# Power_Supply.net
KiCad netlist of a schematic drawn in Altium Designer
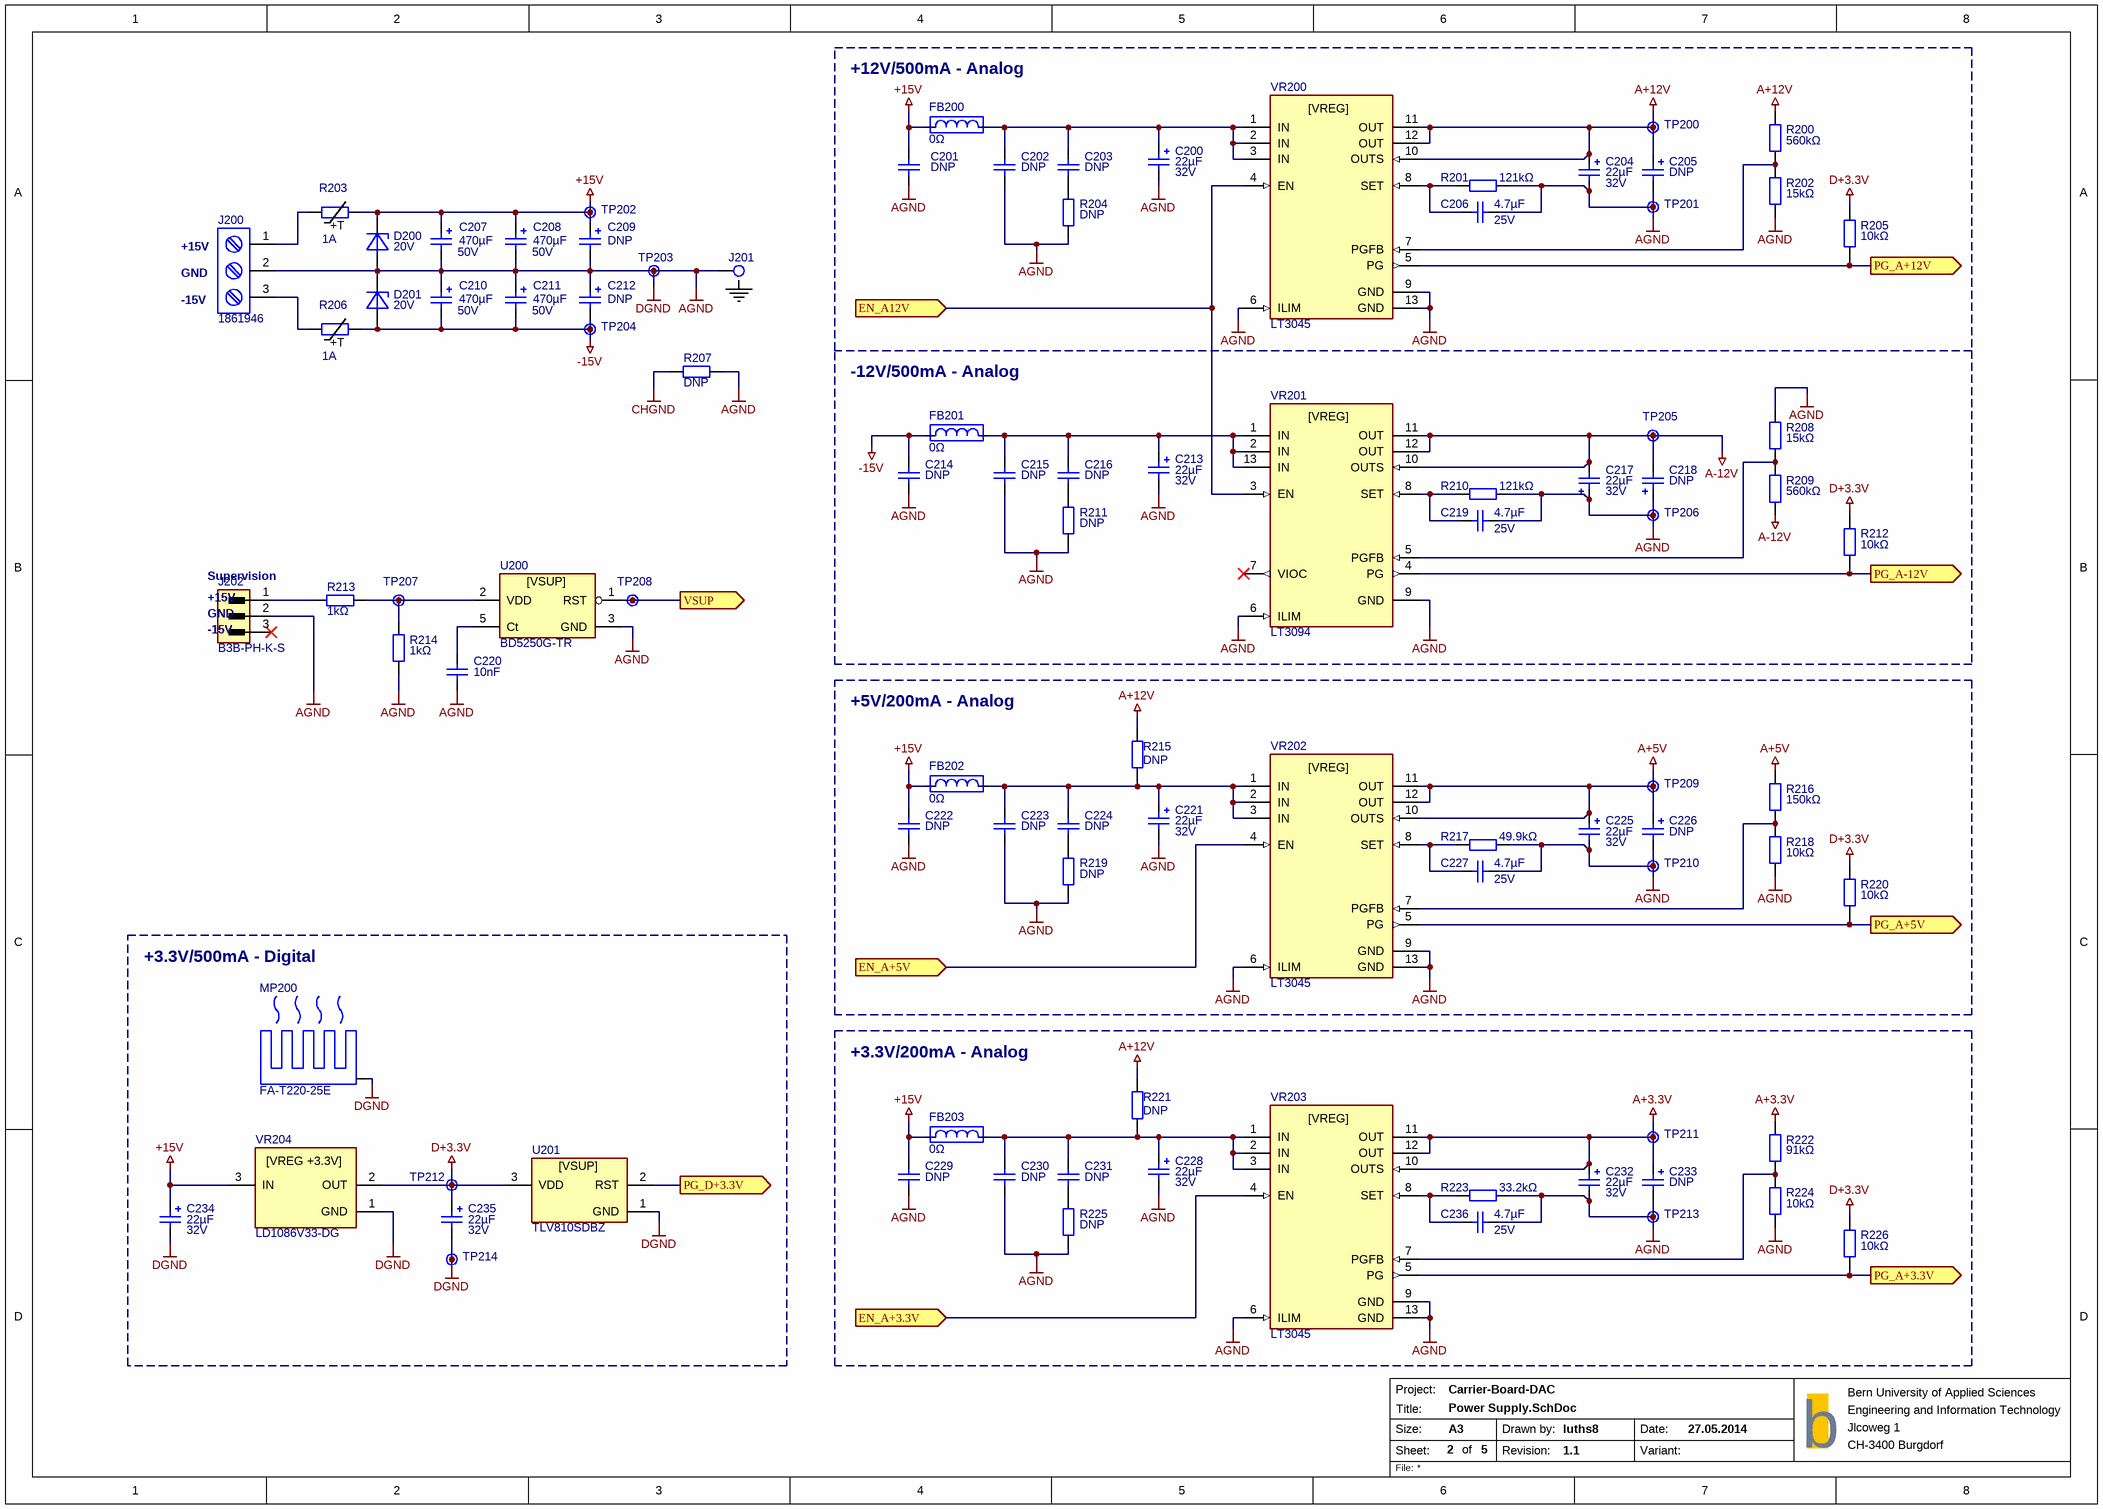
[diagram p0: Power Supply.SchDoc]

(export (version "E")
  (design (tool "Eeschema 10.0.6"))
  (components
    (comp (ref "C200")
      (value "22µF")
      (footprint "CAP-6.3-5.5-2.5")
      (description "Elektrolytic Capacitor")
      (fields (field (name "VOLTAGE") "32V") (field (name "MANUFACTURER PART NO.") "32SEPF22M"))
      (libsource (lib "Audio-Streamer") (part "Capacitor Electrolytic"))
    )
    (comp (ref "C201")
      (value "DNP")
      (footprint "SMD0805CAP")
      (description "Ceramic Capacitor")
      (fields (field (name "VOLTAGE") "25V"))
      (libsource (lib "Audio-Streamer") (part "Capacitor Ceramic"))
    )
    (comp (ref "C202")
      (value "DNP")
      (footprint "SMD0805CAP")
      (description "Ceramic Capacitor")
      (fields (field (name "VOLTAGE") "25V"))
      (libsource (lib "Audio-Streamer") (part "Capacitor Ceramic"))
    )
    (comp (ref "C203")
      (value "DNP")
      (footprint "SMD0805CAP")
      (description "Ceramic Capacitor")
      (fields (field (name "VOLTAGE") "25V"))
      (libsource (lib "Audio-Streamer") (part "Capacitor Ceramic"))
    )
    (comp (ref "C204")
      (value "22µF")
      (footprint "CAP-6.3-5.5-2.5")
      (description "Elektrolytic Capacitor")
      (fields (field (name "VOLTAGE") "32V") (field (name "MANUFACTURER PART NO.") "32SEPF22M"))
      (libsource (lib "Audio-Streamer") (part "Capacitor Electrolytic"))
    )
    (comp (ref "C205")
      (value "DNP")
      (footprint "CAP-6.3-5.5-2.5")
      (description "Elektrolytic Capacitor")
      (fields (field (name "VOLTAGE") "32V") (field (name "MANUFACTURER PART NO.") "32SEPF22M"))
      (libsource (lib "Audio-Streamer") (part "Capacitor Electrolytic"))
    )
    (comp (ref "C206")
      (value "4.7µF")
      (footprint "SMD1206CAP")
      (description "Ceramic Capacitor")
      (fields (field (name "VOLTAGE") "25V"))
      (libsource (lib "Audio-Streamer") (part "Capacitor Ceramic"))
    )
    (comp (ref "C207")
      (value "470µF")
      (footprint "CAP-12.5-20-5")
      (description "Elektrolytic Capacitor")
      (fields (field (name "VOLTAGE") "50V") (field (name "MANUFACTURER PART NO.") "EEU-FR1H471"))
      (libsource (lib "Audio-Streamer") (part "Capacitor Electrolytic"))
    )
    (comp (ref "C208")
      (value "470µF")
      (footprint "CAP-12.5-20-5")
      (description "Elektrolytic Capacitor")
      (fields (field (name "VOLTAGE") "50V") (field (name "MANUFACTURER PART NO.") "EEU-FR1H471"))
      (libsource (lib "Audio-Streamer") (part "Capacitor Electrolytic"))
    )
    (comp (ref "C209")
      (value "DNP")
      (footprint "CAP-12.5-20-5")
      (description "Elektrolytic Capacitor")
      (fields (field (name "VOLTAGE") "50V") (field (name "MANUFACTURER PART NO.") "EEU-FR1H471"))
      (libsource (lib "Audio-Streamer") (part "Capacitor Electrolytic"))
    )
    (comp (ref "C210")
      (value "470µF")
      (footprint "CAP-12.5-20-5")
      (description "Elektrolytic Capacitor")
      (fields (field (name "VOLTAGE") "50V") (field (name "MANUFACTURER PART NO.") "EEU-FR1H471"))
      (libsource (lib "Audio-Streamer") (part "Capacitor Electrolytic"))
    )
    (comp (ref "C211")
      (value "470µF")
      (footprint "CAP-12.5-20-5")
      (description "Elektrolytic Capacitor")
      (fields (field (name "VOLTAGE") "50V") (field (name "MANUFACTURER PART NO.") "EEU-FR1H471"))
      (libsource (lib "Audio-Streamer") (part "Capacitor Electrolytic"))
    )
    (comp (ref "C212")
      (value "DNP")
      (footprint "CAP-12.5-20-5")
      (description "Elektrolytic Capacitor")
      (fields (field (name "VOLTAGE") "50V") (field (name "MANUFACTURER PART NO.") "EEU-FR1H471"))
      (libsource (lib "Audio-Streamer") (part "Capacitor Electrolytic"))
    )
    (comp (ref "C213")
      (value "22µF")
      (footprint "CAP-6.3-5.5-2.5")
      (description "Elektrolytic Capacitor")
      (fields (field (name "VOLTAGE") "32V") (field (name "MANUFACTURER PART NO.") "32SEPF22M"))
      (libsource (lib "Audio-Streamer") (part "Capacitor Electrolytic"))
    )
    (comp (ref "C214")
      (value "DNP")
      (footprint "SMD0805CAP")
      (description "Ceramic Capacitor")
      (fields (field (name "VOLTAGE") "25V"))
      (libsource (lib "Audio-Streamer") (part "Capacitor Ceramic"))
    )
    (comp (ref "C215")
      (value "DNP")
      (footprint "SMD0805CAP")
      (description "Ceramic Capacitor")
      (fields (field (name "VOLTAGE") "25V"))
      (libsource (lib "Audio-Streamer") (part "Capacitor Ceramic"))
    )
    (comp (ref "C216")
      (value "DNP")
      (footprint "SMD0805CAP")
      (description "Ceramic Capacitor")
      (fields (field (name "VOLTAGE") "25V"))
      (libsource (lib "Audio-Streamer") (part "Capacitor Ceramic"))
    )
    (comp (ref "C217")
      (value "22µF")
      (footprint "CAP-6.3-5.5-2.5")
      (description "Elektrolytic Capacitor")
      (fields (field (name "VOLTAGE") "32V") (field (name "MANUFACTURER PART NO.") "32SEPF22M"))
      (libsource (lib "Audio-Streamer") (part "Capacitor Electrolytic"))
    )
    (comp (ref "C218")
      (value "DNP")
      (footprint "CAP-6.3-5.5-2.5")
      (description "Elektrolytic Capacitor")
      (fields (field (name "VOLTAGE") "32V") (field (name "MANUFACTURER PART NO.") "32SEPF22M"))
      (libsource (lib "Audio-Streamer") (part "Capacitor Electrolytic"))
    )
    (comp (ref "C219")
      (value "4.7µF")
      (footprint "SMD1206CAP")
      (description "Ceramic Capacitor")
      (fields (field (name "VOLTAGE") "25V"))
      (libsource (lib "Audio-Streamer") (part "Capacitor Ceramic"))
    )
    (comp (ref "C220")
      (value "10nF")
      (footprint "SMD0603CAP")
      (description "Ceramic Capacitor")
      (fields (field (name "VOLTAGE") "25V"))
      (libsource (lib "Audio-Streamer") (part "Capacitor Ceramic"))
    )
    (comp (ref "C221")
      (value "22µF")
      (footprint "CAP-6.3-5.5-2.5")
      (description "Elektrolytic Capacitor")
      (fields (field (name "VOLTAGE") "32V") (field (name "MANUFACTURER PART NO.") "32SEPF22M"))
      (libsource (lib "Audio-Streamer") (part "Capacitor Electrolytic"))
    )
    (comp (ref "C222")
      (value "DNP")
      (footprint "SMD0805CAP")
      (description "Ceramic Capacitor")
      (fields (field (name "VOLTAGE") "25V"))
      (libsource (lib "Audio-Streamer") (part "Capacitor Ceramic"))
    )
    (comp (ref "C223")
      (value "DNP")
      (footprint "SMD0805CAP")
      (description "Ceramic Capacitor")
      (fields (field (name "VOLTAGE") "25V"))
      (libsource (lib "Audio-Streamer") (part "Capacitor Ceramic"))
    )
    (comp (ref "C224")
      (value "DNP")
      (footprint "SMD0805CAP")
      (description "Ceramic Capacitor")
      (fields (field (name "VOLTAGE") "25V"))
      (libsource (lib "Audio-Streamer") (part "Capacitor Ceramic"))
    )
    (comp (ref "C225")
      (value "22µF")
      (footprint "CAP-6.3-5.5-2.5")
      (description "Elektrolytic Capacitor")
      (fields (field (name "VOLTAGE") "32V") (field (name "MANUFACTURER PART NO.") "32SEPF22M"))
      (libsource (lib "Audio-Streamer") (part "Capacitor Electrolytic"))
    )
    (comp (ref "C226")
      (value "DNP")
      (footprint "CAP-6.3-5.5-2.5")
      (description "Elektrolytic Capacitor")
      (fields (field (name "VOLTAGE") "32V") (field (name "MANUFACTURER PART NO.") "32SEPF22M"))
      (libsource (lib "Audio-Streamer") (part "Capacitor Electrolytic"))
    )
    (comp (ref "C227")
      (value "4.7µF")
      (footprint "SMD1206CAP")
      (description "Ceramic Capacitor")
      (fields (field (name "VOLTAGE") "25V"))
      (libsource (lib "Audio-Streamer") (part "Capacitor Ceramic"))
    )
    (comp (ref "C228")
      (value "22µF")
      (footprint "CAP-6.3-5.5-2.5")
      (description "Elektrolytic Capacitor")
      (fields (field (name "VOLTAGE") "32V") (field (name "MANUFACTURER PART NO.") "32SEPF22M"))
      (libsource (lib "Audio-Streamer") (part "Capacitor Electrolytic"))
    )
    (comp (ref "C229")
      (value "DNP")
      (footprint "SMD0805CAP")
      (description "Ceramic Capacitor")
      (fields (field (name "VOLTAGE") "25V"))
      (libsource (lib "Audio-Streamer") (part "Capacitor Ceramic"))
    )
    (comp (ref "C230")
      (value "DNP")
      (footprint "SMD0805CAP")
      (description "Ceramic Capacitor")
      (fields (field (name "VOLTAGE") "25V"))
      (libsource (lib "Audio-Streamer") (part "Capacitor Ceramic"))
    )
    (comp (ref "C231")
      (value "DNP")
      (footprint "SMD0805CAP")
      (description "Ceramic Capacitor")
      (fields (field (name "VOLTAGE") "25V"))
      (libsource (lib "Audio-Streamer") (part "Capacitor Ceramic"))
    )
    (comp (ref "C232")
      (value "22µF")
      (footprint "CAP-6.3-5.5-2.5")
      (description "Elektrolytic Capacitor")
      (fields (field (name "VOLTAGE") "32V") (field (name "MANUFACTURER PART NO.") "32SEPF22M"))
      (libsource (lib "Audio-Streamer") (part "Capacitor Electrolytic"))
    )
    (comp (ref "C233")
      (value "DNP")
      (footprint "CAP-6.3-5.5-2.5")
      (description "Elektrolytic Capacitor")
      (fields (field (name "VOLTAGE") "32V") (field (name "MANUFACTURER PART NO.") "32SEPF22M"))
      (libsource (lib "Audio-Streamer") (part "Capacitor Electrolytic"))
    )
    (comp (ref "C234")
      (value "22µF")
      (footprint "CAP-6.3-5.5-2.5")
      (description "Elektrolytic Capacitor")
      (fields (field (name "VOLTAGE") "32V") (field (name "MANUFACTURER PART NO.") "32SEPF22M"))
      (libsource (lib "Audio-Streamer") (part "Capacitor Electrolytic"))
    )
    (comp (ref "C235")
      (value "22µF")
      (footprint "CAP-6.3-5.5-2.5")
      (description "Elektrolytic Capacitor")
      (fields (field (name "VOLTAGE") "32V") (field (name "MANUFACTURER PART NO.") "32SEPF22M"))
      (libsource (lib "Audio-Streamer") (part "Capacitor Electrolytic"))
    )
    (comp (ref "C236")
      (value "4.7µF")
      (footprint "SMD1206CAP")
      (description "Ceramic Capacitor")
      (fields (field (name "VOLTAGE") "25V"))
      (libsource (lib "Audio-Streamer") (part "Capacitor Ceramic"))
    )
    (comp (ref "D200")
      (value "20V")
      (footprint "DO-214AA")
      (description "Zener Diode")
      (fields (field (name "MANUFACTURER PART NO.") "SMBJ5357B-TP"))
      (libsource (lib "Audio-Streamer") (part "Diode Zener"))
    )
    (comp (ref "D201")
      (value "20V")
      (footprint "DO-214AA")
      (description "Zener Diode")
      (fields (field (name "MANUFACTURER PART NO.") "SMBJ5357B-TP"))
      (libsource (lib "Audio-Streamer") (part "Diode Zener"))
    )
    (comp (ref "FB200")
      (value "0Ω")
      (footprint "SMD0603RES")
      (description "Ferrite Bead")
      (libsource (lib "Audio-Streamer") (part "Ferrite Bead"))
    )
    (comp (ref "FB201")
      (value "0Ω")
      (footprint "SMD0603RES")
      (description "Ferrite Bead")
      (libsource (lib "Audio-Streamer") (part "Ferrite Bead"))
    )
    (comp (ref "FB202")
      (value "0Ω")
      (footprint "SMD0603RES")
      (description "Ferrite Bead")
      (libsource (lib "Audio-Streamer") (part "Ferrite Bead"))
    )
    (comp (ref "FB203")
      (value "0Ω")
      (footprint "SMD0603RES")
      (description "Ferrite Bead")
      (libsource (lib "Audio-Streamer") (part "Ferrite Bead"))
    )
    (comp (ref "J200")
      (value "1861946")
      (footprint "1861946")
      (description "Screw Terminal, 3 Position")
      (libsource (lib "Audio-Streamer") (part "1861946"))
    )
    (comp (ref "J201")
      (value "Solder Pin")
      (footprint "SOLDER_PIN")
      (libsource (lib "Audio-Streamer") (part "Solder Pin"))
    )
    (comp (ref "J202")
      (value "B3B-PH-K-S")
      (footprint "B3B-PH-K-S")
      (description "Connector 3x1P")
      (libsource (lib "Audio-Streamer") (part "Connector 3x1P"))
    )
    (comp (ref "MP200")
      (value "FA-T220-25E")
      (footprint "FA-T220-25E")
      (description "Heatsink")
      (libsource (lib "Audio-Streamer") (part "Heatsink"))
    )
    (comp (ref "R200")
      (value "560kΩ")
      (footprint "SMD0603RES")
      (description "Resistor")
      (libsource (lib "Audio-Streamer") (part "Resistor"))
    )
    (comp (ref "R201")
      (value "121kΩ")
      (footprint "SMD0603RES")
      (description "Resistor")
      (libsource (lib "") (part "Resistor_2"))
    )
    (comp (ref "R202")
      (value "15kΩ")
      (footprint "SMD0603RES")
      (description "Resistor")
      (libsource (lib "Audio-Streamer") (part "Resistor"))
    )
    (comp (ref "R203")
      (value "1A")
      (footprint "SMD2920FUSE")
      (description "Polyfuse")
      (fields (field (name "MANUFACTURER PART NO.") "0ZCF0100AF2A"))
      (libsource (lib "Audio-Streamer") (part "Polyfuse"))
    )
    (comp (ref "R204")
      (value "DNP")
      (footprint "SMD0603RES")
      (description "Resistor")
      (libsource (lib "Audio-Streamer") (part "Resistor"))
    )
    (comp (ref "R205")
      (value "10kΩ")
      (footprint "SMD0603RES")
      (description "Resistor")
      (libsource (lib "Audio-Streamer") (part "Resistor"))
    )
    (comp (ref "R206")
      (value "1A")
      (footprint "SMD2920FUSE")
      (description "Polyfuse")
      (fields (field (name "MANUFACTURER PART NO.") "0ZCF0100AF2A"))
      (libsource (lib "Audio-Streamer") (part "Polyfuse"))
    )
    (comp (ref "R207")
      (value "DNP")
      (footprint "SMD0805RES")
      (description "Resistor")
      (libsource (lib "") (part "Resistor_3"))
    )
    (comp (ref "R208")
      (value "15kΩ")
      (footprint "SMD0603RES")
      (description "Resistor")
      (libsource (lib "") (part "Resistor_3"))
    )
    (comp (ref "R209")
      (value "560kΩ")
      (footprint "SMD0603RES")
      (description "Resistor")
      (libsource (lib "") (part "Resistor_3"))
    )
    (comp (ref "R210")
      (value "121kΩ")
      (footprint "SMD0603RES")
      (description "Resistor")
      (libsource (lib "") (part "Resistor_2"))
    )
    (comp (ref "R211")
      (value "DNP")
      (footprint "SMD0603RES")
      (description "Resistor")
      (libsource (lib "Audio-Streamer") (part "Resistor"))
    )
    (comp (ref "R212")
      (value "10kΩ")
      (footprint "SMD0603RES")
      (description "Resistor")
      (libsource (lib "Audio-Streamer") (part "Resistor"))
    )
    (comp (ref "R213")
      (value "1kΩ")
      (footprint "SMD0603RES")
      (description "Resistor")
      (libsource (lib "") (part "Resistor_3"))
    )
    (comp (ref "R214")
      (value "1kΩ")
      (footprint "SMD0603RES")
      (description "Resistor")
      (libsource (lib "Audio-Streamer") (part "Resistor"))
    )
    (comp (ref "R215")
      (value "DNP")
      (footprint "SMD0603RES")
      (description "Resistor")
      (libsource (lib "") (part "Resistor_1"))
    )
    (comp (ref "R216")
      (value "150kΩ")
      (footprint "SMD0603RES")
      (description "Resistor")
      (libsource (lib "Audio-Streamer") (part "Resistor"))
    )
    (comp (ref "R217")
      (value "49.9kΩ")
      (footprint "SMD0603RES")
      (description "Resistor")
      (libsource (lib "") (part "Resistor_2"))
    )
    (comp (ref "R218")
      (value "10kΩ")
      (footprint "SMD0603RES")
      (description "Resistor")
      (libsource (lib "Audio-Streamer") (part "Resistor"))
    )
    (comp (ref "R219")
      (value "DNP")
      (footprint "SMD0603RES")
      (description "Resistor")
      (libsource (lib "Audio-Streamer") (part "Resistor"))
    )
    (comp (ref "R220")
      (value "10kΩ")
      (footprint "SMD0603RES")
      (description "Resistor")
      (libsource (lib "Audio-Streamer") (part "Resistor"))
    )
    (comp (ref "R221")
      (value "DNP")
      (footprint "SMD0603RES")
      (description "Resistor")
      (libsource (lib "") (part "Resistor_1"))
    )
    (comp (ref "R222")
      (value "91kΩ")
      (footprint "SMD0603RES")
      (description "Resistor")
      (libsource (lib "Audio-Streamer") (part "Resistor"))
    )
    (comp (ref "R223")
      (value "33.2kΩ")
      (footprint "SMD0603RES")
      (description "Resistor")
      (libsource (lib "") (part "Resistor_2"))
    )
    (comp (ref "R224")
      (value "10kΩ")
      (footprint "SMD0603RES")
      (description "Resistor")
      (libsource (lib "Audio-Streamer") (part "Resistor"))
    )
    (comp (ref "R225")
      (value "DNP")
      (footprint "SMD0603RES")
      (description "Resistor")
      (libsource (lib "Audio-Streamer") (part "Resistor"))
    )
    (comp (ref "R226")
      (value "10kΩ")
      (footprint "SMD0603RES")
      (description "Resistor")
      (libsource (lib "Audio-Streamer") (part "Resistor"))
    )
    (comp (ref "TP200")
      (value "Testpoint")
      (footprint "TP")
      (libsource (lib "Audio-Streamer") (part "Testpoint"))
    )
    (comp (ref "TP201")
      (value "Testpoint")
      (footprint "TP")
      (libsource (lib "Audio-Streamer") (part "Testpoint"))
    )
    (comp (ref "TP202")
      (value "Testpoint")
      (footprint "TP")
      (libsource (lib "Audio-Streamer") (part "Testpoint"))
    )
    (comp (ref "TP203")
      (value "Testpoint")
      (footprint "TP")
      (libsource (lib "Audio-Streamer") (part "Testpoint"))
    )
    (comp (ref "TP204")
      (value "Testpoint")
      (footprint "TP")
      (libsource (lib "Audio-Streamer") (part "Testpoint"))
    )
    (comp (ref "TP205")
      (value "Testpoint")
      (footprint "TP")
      (libsource (lib "Audio-Streamer") (part "Testpoint"))
    )
    (comp (ref "TP206")
      (value "Testpoint")
      (footprint "TP")
      (libsource (lib "Audio-Streamer") (part "Testpoint"))
    )
    (comp (ref "TP207")
      (value "Testpoint")
      (footprint "TP")
      (libsource (lib "Audio-Streamer") (part "Testpoint"))
    )
    (comp (ref "TP208")
      (value "Testpoint")
      (footprint "TP")
      (libsource (lib "Audio-Streamer") (part "Testpoint"))
    )
    (comp (ref "TP209")
      (value "Testpoint")
      (footprint "TP")
      (libsource (lib "Audio-Streamer") (part "Testpoint"))
    )
    (comp (ref "TP210")
      (value "Testpoint")
      (footprint "TP")
      (libsource (lib "Audio-Streamer") (part "Testpoint"))
    )
    (comp (ref "TP211")
      (value "Testpoint")
      (footprint "TP")
      (libsource (lib "Audio-Streamer") (part "Testpoint"))
    )
    (comp (ref "TP212")
      (value "Testpoint")
      (footprint "TP")
      (libsource (lib "Audio-Streamer") (part "Testpoint"))
    )
    (comp (ref "TP213")
      (value "Testpoint")
      (footprint "TP")
      (libsource (lib "Audio-Streamer") (part "Testpoint"))
    )
    (comp (ref "TP214")
      (value "Testpoint")
      (footprint "TP")
      (libsource (lib "Audio-Streamer") (part "Testpoint"))
    )
    (comp (ref "U200")
      (value "BD5250G-TR")
      (footprint "SOT-23-5")
      (description "Voltage Supervisor, Threshold 5V")
      (libsource (lib "Audio-Streamer") (part "Voltage Supervisor 5V"))
    )
    (comp (ref "U201")
      (value "TLV810SDBZ")
      (footprint "SOT-23")
      (description "Voltage Supervisor, Threshold 2.94V")
      (fields (field (name "MANUFACTURER PART NO.") "TLV810SDBZR"))
      (libsource (lib "Audio-Streamer") (part "Voltage Supervisor"))
    )
    (comp (ref "VR200")
      (value "LT3045")
      (footprint "MSOP12")
      (description "Linear Regulator, positive Rail, Low Noise, High PSRR")
      (fields (field (name "MANUFACTURER PART NO.") "LT3045EMSE#PBF"))
      (libsource (lib "Audio-Streamer") (part "LT3045"))
    )
    (comp (ref "VR201")
      (value "LT3094")
      (footprint "MSOP12")
      (description "Linear Regulator, negative Rail Low Noise, High PSRR")
      (fields (field (name "MANUFACTURER PART NO.") "LT3094EMSE#PBF"))
      (libsource (lib "Audio-Streamer") (part "LT3094"))
    )
    (comp (ref "VR202")
      (value "LT3045")
      (footprint "MSOP12")
      (description "Linear Regulator, positive Rail, Low Noise, High PSRR")
      (fields (field (name "MANUFACTURER PART NO.") "LT3045EMSE#PBF"))
      (libsource (lib "Audio-Streamer") (part "LT3045"))
    )
    (comp (ref "VR203")
      (value "LT3045")
      (footprint "MSOP12")
      (description "Linear Regulator, positive Rail, Low Noise, High PSRR")
      (fields (field (name "MANUFACTURER PART NO.") "LT3045EMSE#PBF"))
      (libsource (lib "Audio-Streamer") (part "LT3045"))
    )
    (comp (ref "VR204")
      (value "LD1086V33-DG")
      (footprint "TO220-3")
      (description "Linear Voltage Regulator, positive Rail")
      (libsource (lib "Audio-Streamer") (part "LD1086V33-DG"))
    )
  )
  (nets
    (net (code "1") (name "+15V") (class "Default")
      (node (ref "C201") (pin "2") (pinfunction "q_2") (pintype "passive"))
      (node (ref "C207") (pin "P") (pinfunction "P_P") (pintype "passive"))
      (node (ref "C208") (pin "P") (pinfunction "P_P") (pintype "passive"))
      (node (ref "C209") (pin "P") (pinfunction "P_P") (pintype "passive"))
      (node (ref "C222") (pin "2") (pinfunction "q_2") (pintype "passive"))
      (node (ref "C229") (pin "2") (pinfunction "q_2") (pintype "passive"))
      (node (ref "C234") (pin "P") (pinfunction "P_P") (pintype "passive"))
      (node (ref "D200") (pin "C") (pinfunction "C_C") (pintype "passive"))
      (node (ref "FB200") (pin "1") (pinfunction "1_1") (pintype "passive"))
      (node (ref "FB202") (pin "1") (pinfunction "1_1") (pintype "passive"))
      (node (ref "FB203") (pin "1") (pinfunction "1_1") (pintype "passive"))
      (node (ref "R203") (pin "2") (pinfunction "2_2") (pintype "passive"))
      (node (ref "TP202") (pin "1") (pinfunction "1_1") (pintype "passive"))
      (node (ref "VR204") (pin "3") (pinfunction "IN_3") (pintype "power_in"))
    )
    (net (code "2") (name "-15V") (class "Default")
      (node (ref "C210") (pin "M") (pinfunction "q_M") (pintype "passive"))
      (node (ref "C211") (pin "M") (pinfunction "q_M") (pintype "passive"))
      (node (ref "C212") (pin "M") (pinfunction "q_M") (pintype "passive"))
      (node (ref "C214") (pin "2") (pinfunction "q_2") (pintype "passive"))
      (node (ref "D201") (pin "A") (pinfunction "A_A") (pintype "passive"))
      (node (ref "FB201") (pin "1") (pinfunction "1_1") (pintype "passive"))
      (node (ref "R206") (pin "2") (pinfunction "2_2") (pintype "passive"))
      (node (ref "TP204") (pin "1") (pinfunction "1_1") (pintype "passive"))
    )
    (net (code "3") (name "/EN_A+3.3V") (class "Default")
      (node (ref "VR203") (pin "4") (pinfunction "EN_4") (pintype "input"))
    )
    (net (code "4") (name "/EN_A+5V") (class "Default")
      (node (ref "VR202") (pin "4") (pinfunction "EN_4") (pintype "input"))
    )
    (net (code "5") (name "/EN_A12V") (class "Default")
      (node (ref "VR200") (pin "4") (pinfunction "EN_4") (pintype "input"))
      (node (ref "VR201") (pin "3") (pinfunction "EN_3") (pintype "input"))
    )
    (net (code "6") (name "/PG_A+3.3V") (class "Default")
      (node (ref "R226") (pin "1") (pinfunction "1_1") (pintype "passive"))
      (node (ref "VR203") (pin "5") (pinfunction "PG_5") (pintype "output"))
    )
    (net (code "7") (name "/PG_A+5V") (class "Default")
      (node (ref "R220") (pin "1") (pinfunction "1_1") (pintype "passive"))
      (node (ref "VR202") (pin "5") (pinfunction "PG_5") (pintype "output"))
    )
    (net (code "8") (name "/PG_A+12V") (class "Default")
      (node (ref "R205") (pin "1") (pinfunction "1_1") (pintype "passive"))
      (node (ref "VR200") (pin "5") (pinfunction "PG_5") (pintype "output"))
    )
    (net (code "9") (name "/PG_A-12V") (class "Default")
      (node (ref "R212") (pin "1") (pinfunction "1_1") (pintype "passive"))
      (node (ref "VR201") (pin "4") (pinfunction "PG_4") (pintype "output"))
    )
    (net (code "10") (name "/PG_D+3.3V") (class "Default")
      (node (ref "U201") (pin "2") (pinfunction "RST_2") (pintype "passive"))
    )
    (net (code "11") (name "/VSUP") (class "Default")
      (node (ref "TP208") (pin "1") (pinfunction "1_1") (pintype "passive"))
      (node (ref "U200") (pin "1") (pinfunction "RST_1") (pintype "open_collector"))
    )
    (net (code "12") (name "A+3.3V") (class "Default")
      (node (ref "C232") (pin "P") (pinfunction "P_P") (pintype "passive"))
      (node (ref "C233") (pin "P") (pinfunction "P_P") (pintype "passive"))
      (node (ref "R222") (pin "2") (pinfunction "2_2") (pintype "passive"))
      (node (ref "TP211") (pin "1") (pinfunction "1_1") (pintype "passive"))
      (node (ref "VR203") (pin "10") (pinfunction "OUTS_10") (pintype "input"))
      (node (ref "VR203") (pin "11") (pinfunction "OUT_11") (pintype "power_in"))
      (node (ref "VR203") (pin "12") (pinfunction "OUT_12") (pintype "power_in"))
    )
    (net (code "13") (name "A+5V") (class "Default")
      (node (ref "C225") (pin "P") (pinfunction "P_P") (pintype "passive"))
      (node (ref "C226") (pin "P") (pinfunction "P_P") (pintype "passive"))
      (node (ref "R216") (pin "2") (pinfunction "2_2") (pintype "passive"))
      (node (ref "TP209") (pin "1") (pinfunction "1_1") (pintype "passive"))
      (node (ref "VR202") (pin "10") (pinfunction "OUTS_10") (pintype "input"))
      (node (ref "VR202") (pin "11") (pinfunction "OUT_11") (pintype "power_in"))
      (node (ref "VR202") (pin "12") (pinfunction "OUT_12") (pintype "power_in"))
    )
    (net (code "14") (name "A+12V") (class "Default")
      (node (ref "C204") (pin "P") (pinfunction "P_P") (pintype "passive"))
      (node (ref "C205") (pin "P") (pinfunction "P_P") (pintype "passive"))
      (node (ref "R200") (pin "2") (pinfunction "2_2") (pintype "passive"))
      (node (ref "R215") (pin "1") (pinfunction "1_1") (pintype "passive"))
      (node (ref "R221") (pin "1") (pinfunction "1_1") (pintype "passive"))
      (node (ref "TP200") (pin "1") (pinfunction "1_1") (pintype "passive"))
      (node (ref "VR200") (pin "10") (pinfunction "OUTS_10") (pintype "input"))
      (node (ref "VR200") (pin "11") (pinfunction "OUT_11") (pintype "power_in"))
      (node (ref "VR200") (pin "12") (pinfunction "OUT_12") (pintype "power_in"))
    )
    (net (code "15") (name "A-12V") (class "Default")
      (node (ref "C217") (pin "M") (pinfunction "q_M") (pintype "passive"))
      (node (ref "C218") (pin "M") (pinfunction "q_M") (pintype "passive"))
      (node (ref "R209") (pin "2") (pinfunction "2_2") (pintype "passive"))
      (node (ref "TP205") (pin "1") (pinfunction "1_1") (pintype "passive"))
      (node (ref "VR201") (pin "10") (pinfunction "OUTS_10") (pintype "input"))
      (node (ref "VR201") (pin "11") (pinfunction "OUT_11") (pintype "power_in"))
      (node (ref "VR201") (pin "12") (pinfunction "OUT_12") (pintype "power_in"))
    )
    (net (code "16") (name "AGND") (class "Default")
      (node (ref "C200") (pin "M") (pinfunction "q_M") (pintype "passive"))
      (node (ref "C201") (pin "1") (pinfunction "1_1") (pintype "passive"))
      (node (ref "C202") (pin "1") (pinfunction "1_1") (pintype "passive"))
      (node (ref "C204") (pin "M") (pinfunction "q_M") (pintype "passive"))
      (node (ref "C205") (pin "M") (pinfunction "q_M") (pintype "passive"))
      (node (ref "C206") (pin "2") (pinfunction "q_2") (pintype "passive"))
      (node (ref "C207") (pin "M") (pinfunction "q_M") (pintype "passive"))
      (node (ref "C208") (pin "M") (pinfunction "q_M") (pintype "passive"))
      (node (ref "C209") (pin "M") (pinfunction "q_M") (pintype "passive"))
      (node (ref "C210") (pin "P") (pinfunction "P_P") (pintype "passive"))
      (node (ref "C211") (pin "P") (pinfunction "P_P") (pintype "passive"))
      (node (ref "C212") (pin "P") (pinfunction "P_P") (pintype "passive"))
      (node (ref "C213") (pin "M") (pinfunction "q_M") (pintype "passive"))
      (node (ref "C214") (pin "1") (pinfunction "1_1") (pintype "passive"))
      (node (ref "C215") (pin "1") (pinfunction "1_1") (pintype "passive"))
      (node (ref "C217") (pin "P") (pinfunction "P_P") (pintype "passive"))
      (node (ref "C218") (pin "P") (pinfunction "P_P") (pintype "passive"))
      (node (ref "C219") (pin "2") (pinfunction "q_2") (pintype "passive"))
      (node (ref "C220") (pin "1") (pinfunction "1_1") (pintype "passive"))
      (node (ref "C221") (pin "M") (pinfunction "q_M") (pintype "passive"))
      (node (ref "C222") (pin "1") (pinfunction "1_1") (pintype "passive"))
      (node (ref "C223") (pin "1") (pinfunction "1_1") (pintype "passive"))
      (node (ref "C225") (pin "M") (pinfunction "q_M") (pintype "passive"))
      (node (ref "C226") (pin "M") (pinfunction "q_M") (pintype "passive"))
      (node (ref "C227") (pin "2") (pinfunction "q_2") (pintype "passive"))
      (node (ref "C228") (pin "M") (pinfunction "q_M") (pintype "passive"))
      (node (ref "C229") (pin "1") (pinfunction "1_1") (pintype "passive"))
      (node (ref "C230") (pin "1") (pinfunction "1_1") (pintype "passive"))
      (node (ref "C232") (pin "M") (pinfunction "q_M") (pintype "passive"))
      (node (ref "C233") (pin "M") (pinfunction "q_M") (pintype "passive"))
      (node (ref "C234") (pin "M") (pinfunction "q_M") (pintype "passive"))
      (node (ref "C235") (pin "M") (pinfunction "q_M") (pintype "passive"))
      (node (ref "C236") (pin "2") (pinfunction "q_2") (pintype "passive"))
      (node (ref "D200") (pin "A") (pinfunction "A_A") (pintype "passive"))
      (node (ref "D201") (pin "C") (pinfunction "C_C") (pintype "passive"))
      (node (ref "J200") (pin "2") (pinfunction "2_2") (pintype "passive"))
      (node (ref "J201") (pin "1") (pinfunction "1_1") (pintype "passive"))
      (node (ref "J202") (pin "2") (pinfunction "2_2") (pintype "passive"))
      (node (ref "MP200") (pin "0") (pinfunction "0_0") (pintype "passive"))
      (node (ref "R201") (pin "2") (pinfunction "2_2") (pintype "passive"))
      (node (ref "R202") (pin "1") (pinfunction "1_1") (pintype "passive"))
      (node (ref "R204") (pin "1") (pinfunction "1_1") (pintype "passive"))
      (node (ref "R207") (pin "1") (pinfunction "1_1") (pintype "passive"))
      (node (ref "R208") (pin "1") (pinfunction "1_1") (pintype "passive"))
      (node (ref "R210") (pin "2") (pinfunction "2_2") (pintype "passive"))
      (node (ref "R211") (pin "1") (pinfunction "1_1") (pintype "passive"))
      (node (ref "R214") (pin "1") (pinfunction "1_1") (pintype "passive"))
      (node (ref "R217") (pin "2") (pinfunction "2_2") (pintype "passive"))
      (node (ref "R218") (pin "1") (pinfunction "1_1") (pintype "passive"))
      (node (ref "R219") (pin "1") (pinfunction "1_1") (pintype "passive"))
      (node (ref "R223") (pin "2") (pinfunction "2_2") (pintype "passive"))
      (node (ref "R224") (pin "1") (pinfunction "1_1") (pintype "passive"))
      (node (ref "R225") (pin "1") (pinfunction "1_1") (pintype "passive"))
      (node (ref "TP201") (pin "1") (pinfunction "1_1") (pintype "passive"))
      (node (ref "TP203") (pin "1") (pinfunction "1_1") (pintype "passive"))
      (node (ref "TP206") (pin "1") (pinfunction "1_1") (pintype "passive"))
      (node (ref "TP210") (pin "1") (pinfunction "1_1") (pintype "passive"))
      (node (ref "TP213") (pin "1") (pinfunction "1_1") (pintype "passive"))
      (node (ref "TP214") (pin "1") (pinfunction "1_1") (pintype "passive"))
      (node (ref "U200") (pin "3") (pinfunction "GND_3") (pintype "passive"))
      (node (ref "U201") (pin "1") (pinfunction "GND_1") (pintype "passive"))
      (node (ref "VR200") (pin "13") (pinfunction "GND_13") (pintype "power_in"))
      (node (ref "VR200") (pin "6") (pinfunction "ILIM_6") (pintype "input"))
      (node (ref "VR200") (pin "9") (pinfunction "GND_9") (pintype "power_in"))
      (node (ref "VR201") (pin "6") (pinfunction "ILIM_6") (pintype "input"))
      (node (ref "VR201") (pin "9") (pinfunction "GND_9") (pintype "power_in"))
      (node (ref "VR202") (pin "13") (pinfunction "GND_13") (pintype "power_in"))
      (node (ref "VR202") (pin "6") (pinfunction "ILIM_6") (pintype "input"))
      (node (ref "VR202") (pin "9") (pinfunction "GND_9") (pintype "power_in"))
      (node (ref "VR203") (pin "13") (pinfunction "GND_13") (pintype "power_in"))
      (node (ref "VR203") (pin "6") (pinfunction "ILIM_6") (pintype "input"))
      (node (ref "VR203") (pin "9") (pinfunction "GND_9") (pintype "power_in"))
      (node (ref "VR204") (pin "1") (pinfunction "GND_1") (pintype "power_in"))
    )
    (net (code "17") (name "CHGND") (class "Default")
      (node (ref "R207") (pin "2") (pinfunction "2_2") (pintype "passive"))
    )
    (net (code "18") (name "D+3.3V") (class "Default")
      (node (ref "C235") (pin "P") (pinfunction "P_P") (pintype "passive"))
      (node (ref "R205") (pin "2") (pinfunction "2_2") (pintype "passive"))
      (node (ref "R212") (pin "2") (pinfunction "2_2") (pintype "passive"))
      (node (ref "R220") (pin "2") (pinfunction "2_2") (pintype "passive"))
      (node (ref "R226") (pin "2") (pinfunction "2_2") (pintype "passive"))
      (node (ref "TP212") (pin "1") (pinfunction "1_1") (pintype "passive"))
      (node (ref "U201") (pin "3") (pinfunction "VDD_3") (pintype "passive"))
      (node (ref "VR204") (pin "2") (pinfunction "OUT_2") (pintype "power_in"))
    )
    (net (code "19") (name "Net-(C202-q)") (class "Default")
      (node (ref "C200") (pin "P") (pinfunction "P_P") (pintype "passive"))
      (node (ref "C202") (pin "2") (pinfunction "q_2") (pintype "passive"))
      (node (ref "C203") (pin "2") (pinfunction "q_2") (pintype "passive"))
      (node (ref "FB200") (pin "2") (pinfunction "2_2") (pintype "passive"))
      (node (ref "VR200") (pin "1") (pinfunction "IN_1") (pintype "power_in"))
      (node (ref "VR200") (pin "2") (pinfunction "IN_2") (pintype "power_in"))
      (node (ref "VR200") (pin "3") (pinfunction "IN_3") (pintype "power_in"))
    )
    (net (code "20") (name "Net-(C203-Pad1)") (class "Default")
      (node (ref "C203") (pin "1") (pinfunction "1_1") (pintype "passive"))
      (node (ref "R204") (pin "2") (pinfunction "2_2") (pintype "passive"))
    )
    (net (code "21") (name "Net-(C215-q)") (class "Default")
      (node (ref "C213") (pin "P") (pinfunction "P_P") (pintype "passive"))
      (node (ref "C215") (pin "2") (pinfunction "q_2") (pintype "passive"))
      (node (ref "C216") (pin "2") (pinfunction "q_2") (pintype "passive"))
      (node (ref "FB201") (pin "2") (pinfunction "2_2") (pintype "passive"))
      (node (ref "VR201") (pin "1") (pinfunction "IN_1") (pintype "power_in"))
      (node (ref "VR201") (pin "13") (pinfunction "IN_13") (pintype "power_in"))
      (node (ref "VR201") (pin "2") (pinfunction "IN_2") (pintype "power_in"))
    )
    (net (code "22") (name "Net-(C216-Pad1)") (class "Default")
      (node (ref "C216") (pin "1") (pinfunction "1_1") (pintype "passive"))
      (node (ref "R211") (pin "2") (pinfunction "2_2") (pintype "passive"))
    )
    (net (code "23") (name "Net-(C220-q)") (class "Default")
      (node (ref "C220") (pin "2") (pinfunction "q_2") (pintype "passive"))
      (node (ref "U200") (pin "5") (pinfunction "Ct_5") (pintype "passive"))
    )
    (net (code "24") (name "Net-(C223-q)") (class "Default")
      (node (ref "C221") (pin "P") (pinfunction "P_P") (pintype "passive"))
      (node (ref "C223") (pin "2") (pinfunction "q_2") (pintype "passive"))
      (node (ref "C224") (pin "2") (pinfunction "q_2") (pintype "passive"))
      (node (ref "FB202") (pin "2") (pinfunction "2_2") (pintype "passive"))
      (node (ref "R215") (pin "2") (pinfunction "2_2") (pintype "passive"))
      (node (ref "VR202") (pin "1") (pinfunction "IN_1") (pintype "power_in"))
      (node (ref "VR202") (pin "2") (pinfunction "IN_2") (pintype "power_in"))
      (node (ref "VR202") (pin "3") (pinfunction "IN_3") (pintype "power_in"))
    )
    (net (code "25") (name "Net-(C224-Pad1)") (class "Default")
      (node (ref "C224") (pin "1") (pinfunction "1_1") (pintype "passive"))
      (node (ref "R219") (pin "2") (pinfunction "2_2") (pintype "passive"))
    )
    (net (code "26") (name "Net-(C230-q)") (class "Default")
      (node (ref "C228") (pin "P") (pinfunction "P_P") (pintype "passive"))
      (node (ref "C230") (pin "2") (pinfunction "q_2") (pintype "passive"))
      (node (ref "C231") (pin "2") (pinfunction "q_2") (pintype "passive"))
      (node (ref "FB203") (pin "2") (pinfunction "2_2") (pintype "passive"))
      (node (ref "R221") (pin "2") (pinfunction "2_2") (pintype "passive"))
      (node (ref "VR203") (pin "1") (pinfunction "IN_1") (pintype "power_in"))
      (node (ref "VR203") (pin "2") (pinfunction "IN_2") (pintype "power_in"))
      (node (ref "VR203") (pin "3") (pinfunction "IN_3") (pintype "power_in"))
    )
    (net (code "27") (name "Net-(C231-Pad1)") (class "Default")
      (node (ref "C231") (pin "1") (pinfunction "1_1") (pintype "passive"))
      (node (ref "R225") (pin "2") (pinfunction "2_2") (pintype "passive"))
    )
    (net (code "28") (name "Net-(J200-Pad1)") (class "Default")
      (node (ref "J200") (pin "1") (pinfunction "1_1") (pintype "passive"))
      (node (ref "R203") (pin "1") (pinfunction "1_1") (pintype "passive"))
    )
    (net (code "29") (name "Net-(J200-Pad3)") (class "Default")
      (node (ref "J200") (pin "3") (pinfunction "3_3") (pintype "passive"))
      (node (ref "R206") (pin "1") (pinfunction "1_1") (pintype "passive"))
    )
    (net (code "30") (name "Net-(J202-Pad1)") (class "Default")
      (node (ref "J202") (pin "1") (pinfunction "1_1") (pintype "passive"))
      (node (ref "R213") (pin "2") (pinfunction "2_2") (pintype "passive"))
    )
    (net (code "31") (name "Net-(U200-VDD)") (class "Default")
      (node (ref "R213") (pin "1") (pinfunction "1_1") (pintype "passive"))
      (node (ref "R214") (pin "2") (pinfunction "2_2") (pintype "passive"))
      (node (ref "TP207") (pin "1") (pinfunction "1_1") (pintype "passive"))
      (node (ref "U200") (pin "2") (pinfunction "VDD_2") (pintype "passive"))
    )
    (net (code "32") (name "Net-(VR200-PGFB)") (class "Default")
      (node (ref "R200") (pin "1") (pinfunction "1_1") (pintype "passive"))
      (node (ref "R202") (pin "2") (pinfunction "2_2") (pintype "passive"))
      (node (ref "VR200") (pin "7") (pinfunction "PGFB_7") (pintype "input"))
    )
    (net (code "33") (name "Net-(VR200-SET)") (class "Default")
      (node (ref "C206") (pin "1") (pinfunction "1_1") (pintype "passive"))
      (node (ref "R201") (pin "1") (pinfunction "1_1") (pintype "passive"))
      (node (ref "VR200") (pin "8") (pinfunction "SET_8") (pintype "input"))
    )
    (net (code "34") (name "Net-(VR201-PGFB)") (class "Default")
      (node (ref "R208") (pin "2") (pinfunction "2_2") (pintype "passive"))
      (node (ref "R209") (pin "1") (pinfunction "1_1") (pintype "passive"))
      (node (ref "VR201") (pin "5") (pinfunction "PGFB_5") (pintype "input"))
    )
    (net (code "35") (name "Net-(VR201-SET)") (class "Default")
      (node (ref "C219") (pin "1") (pinfunction "1_1") (pintype "passive"))
      (node (ref "R210") (pin "1") (pinfunction "1_1") (pintype "passive"))
      (node (ref "VR201") (pin "8") (pinfunction "SET_8") (pintype "input"))
    )
    (net (code "36") (name "Net-(VR202-PGFB)") (class "Default")
      (node (ref "R216") (pin "1") (pinfunction "1_1") (pintype "passive"))
      (node (ref "R218") (pin "2") (pinfunction "2_2") (pintype "passive"))
      (node (ref "VR202") (pin "7") (pinfunction "PGFB_7") (pintype "input"))
    )
    (net (code "37") (name "Net-(VR202-SET)") (class "Default")
      (node (ref "C227") (pin "1") (pinfunction "1_1") (pintype "passive"))
      (node (ref "R217") (pin "1") (pinfunction "1_1") (pintype "passive"))
      (node (ref "VR202") (pin "8") (pinfunction "SET_8") (pintype "input"))
    )
    (net (code "38") (name "Net-(VR203-PGFB)") (class "Default")
      (node (ref "R222") (pin "1") (pinfunction "1_1") (pintype "passive"))
      (node (ref "R224") (pin "2") (pinfunction "2_2") (pintype "passive"))
      (node (ref "VR203") (pin "7") (pinfunction "PGFB_7") (pintype "input"))
    )
    (net (code "39") (name "Net-(VR203-SET)") (class "Default")
      (node (ref "C236") (pin "1") (pinfunction "1_1") (pintype "passive"))
      (node (ref "R223") (pin "1") (pinfunction "1_1") (pintype "passive"))
      (node (ref "VR203") (pin "8") (pinfunction "SET_8") (pintype "input"))
    )
    (net (code "40") (name "unconnected-(J202-Pad3)") (class "Default")
      (node (ref "J202") (pin "3") (pinfunction "3_3") (pintype "passive+no_connect"))
    )
    (net (code "41") (name "unconnected-(VR201-VIOC-Pad7)") (class "Default")
      (node (ref "VR201") (pin "7") (pinfunction "VIOC_7") (pintype "output+no_connect"))
    )
  )
)
